# boost_gauge.net
KiCad netlist of a schematic drawn in EAGLE
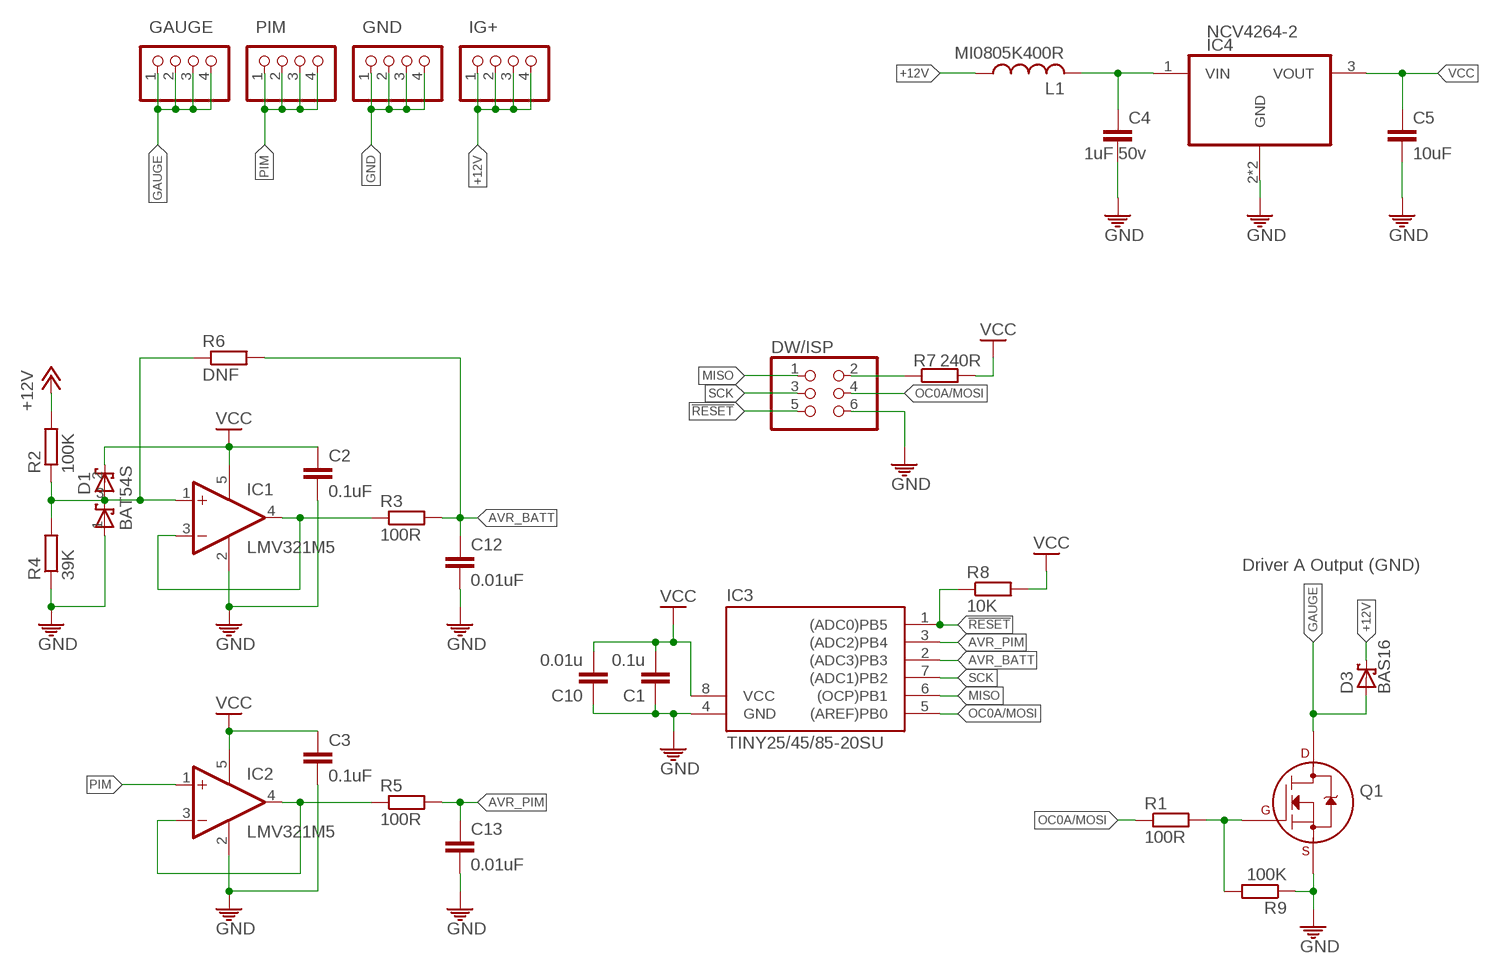
[diagram p0: schematic, sheet 1]

(export (version "E")
  (design (tool "Eeschema 10.0.6"))
  (components
    (comp (ref "C1")
      (value "0.1u")
      (footprint "eagle-import:C0603")
      (libsource (lib "eagle-import") (part "C-EUC0603"))
    )
    (comp (ref "C2")
      (value "0.1uF")
      (footprint "eagle-import:C0603")
      (libsource (lib "eagle-import") (part "C-EUC0603"))
    )
    (comp (ref "C3")
      (value "0.1uF")
      (footprint "eagle-import:C0603")
      (libsource (lib "eagle-import") (part "C-EUC0603"))
    )
    (comp (ref "C4")
      (value "1uF 50v")
      (footprint "eagle-import:C0603")
      (libsource (lib "eagle-import") (part "C-EUC0603"))
    )
    (comp (ref "C5")
      (value "10uF")
      (footprint "eagle-import:C1206")
      (libsource (lib "eagle-import") (part "C-EUC1206"))
    )
    (comp (ref "C10")
      (value "0.01u")
      (footprint "eagle-import:C0603")
      (libsource (lib "eagle-import") (part "C-EUC0603"))
    )
    (comp (ref "C12")
      (value "0.01uF")
      (footprint "eagle-import:C0603")
      (libsource (lib "eagle-import") (part "C-EUC0603"))
    )
    (comp (ref "C13")
      (value "0.01uF")
      (footprint "eagle-import:C0603")
      (libsource (lib "eagle-import") (part "C-EUC0603"))
    )
    (comp (ref "D1")
      (value "BAT54S")
      (footprint "eagle-import:SOT23")
      (libsource (lib "eagle-import") (part "BAT54S"))
    )
    (comp (ref "D3")
      (value "BAS16")
      (footprint "eagle-import:SOT23")
      (libsource (lib "eagle-import") (part "BAS16"))
    )
    (comp (ref "DW/ISP")
      (value "PINHD-2X3")
      (footprint "eagle-import:2X03")
      (libsource (lib "eagle-import") (part "PINHD-2X3"))
    )
    (comp (ref "GAUGE")
      (value "PCB-2")
      (footprint "eagle-import:PCB-2")
      (libsource (lib "eagle-import") (part "PCB-2"))
    )
    (comp (ref "GND")
      (value "PCB-2")
      (footprint "eagle-import:PCB-2")
      (libsource (lib "eagle-import") (part "PCB-2"))
    )
    (comp (ref "IC1")
      (value "LMV321M5")
      (footprint "eagle-import:SOT23-5")
      (libsource (lib "eagle-import") (part "LMV321?M5"))
    )
    (comp (ref "IC2")
      (value "LMV321M5")
      (footprint "eagle-import:SOT23-5")
      (libsource (lib "eagle-import") (part "LMV321?M5"))
    )
    (comp (ref "IC3")
      (value "TINY25/45/85-20SU")
      (footprint "eagle-import:SOIC8")
      (libsource (lib "eagle-import") (part "TINY25/45/85-20SU"))
    )
    (comp (ref "IC4")
      (value "NCV4264-2")
      (footprint "eagle-import:SOT223")
      (libsource (lib "eagle-import") (part "NCV4264-2"))
    )
    (comp (ref "IG+")
      (value "PCB-2")
      (footprint "eagle-import:PCB-2")
      (libsource (lib "eagle-import") (part "PCB-2"))
    )
    (comp (ref "L1")
      (value "MI0805K400R")
      (footprint "eagle-import:R0805")
      (libsource (lib "eagle-import") (part "MI0805K400R"))
    )
    (comp (ref "PIM")
      (value "PCB-2")
      (footprint "eagle-import:PCB-2")
      (libsource (lib "eagle-import") (part "PCB-2"))
    )
    (comp (ref "Q1")
      (value "2N7002A")
      (footprint "eagle-import:SOT23")
      (libsource (lib "eagle-import") (part "2N7002A"))
    )
    (comp (ref "R1")
      (value "100R")
      (footprint "eagle-import:R0603")
      (libsource (lib "eagle-import") (part "R-EU_R0603"))
    )
    (comp (ref "R2")
      (value "100K")
      (footprint "eagle-import:R0603")
      (libsource (lib "eagle-import") (part "R-EU_R0603"))
    )
    (comp (ref "R3")
      (value "100R")
      (footprint "eagle-import:R0603")
      (libsource (lib "eagle-import") (part "R-EU_R0603"))
    )
    (comp (ref "R4")
      (value "39K")
      (footprint "eagle-import:R0603")
      (libsource (lib "eagle-import") (part "R-EU_R0603"))
    )
    (comp (ref "R5")
      (value "100R")
      (footprint "eagle-import:R0603")
      (libsource (lib "eagle-import") (part "R-EU_R0603"))
    )
    (comp (ref "R6")
      (value "DNF")
      (footprint "eagle-import:R0603")
      (libsource (lib "eagle-import") (part "R-EU_R0603"))
    )
    (comp (ref "R7")
      (value "240R")
      (footprint "eagle-import:R0603")
      (libsource (lib "eagle-import") (part "R-EU_R0603"))
    )
    (comp (ref "R8")
      (value "10K")
      (footprint "eagle-import:R0603")
      (libsource (lib "eagle-import") (part "R-EU_R0603"))
    )
    (comp (ref "R9")
      (value "100K")
      (footprint "eagle-import:R0603")
      (libsource (lib "eagle-import") (part "R-EU_R0603"))
    )
  )
  (nets
    (net (code "1") (name "+12V") (class "Default")
      (node (ref "D3") (pin "3") (pinfunction "C_3") (pintype "passive"))
      (node (ref "IG+") (pin "1") (pinfunction "1_1") (pintype "passive"))
      (node (ref "IG+") (pin "2") (pinfunction "2_2") (pintype "passive"))
      (node (ref "IG+") (pin "3") (pinfunction "3_3") (pintype "passive"))
      (node (ref "IG+") (pin "4") (pinfunction "4_4") (pintype "passive"))
      (node (ref "L1") (pin "1") (pinfunction "1_1") (pintype "passive"))
      (node (ref "R2") (pin "2") (pinfunction "2_2") (pintype "passive"))
    )
    (net (code "2") (name "/~{RESET}") (class "Default")
      (node (ref "DW/ISP") (pin "5") (pinfunction "5_5") (pintype "passive"))
      (node (ref "IC3") (pin "1") (pinfunction "(ADC0)PB5_1") (pintype "bidirectional"))
      (node (ref "R8") (pin "1") (pinfunction "1_1") (pintype "passive"))
    )
    (net (code "3") (name "AVR_BATT") (class "Default")
      (node (ref "C12") (pin "1") (pinfunction "1_1") (pintype "passive"))
      (node (ref "IC3") (pin "2") (pinfunction "(ADC3)PB3_2") (pintype "bidirectional"))
      (node (ref "R3") (pin "2") (pinfunction "2_2") (pintype "passive"))
      (node (ref "R6") (pin "2") (pinfunction "2_2") (pintype "passive"))
    )
    (net (code "4") (name "AVR_PIM") (class "Default")
      (node (ref "C13") (pin "1") (pinfunction "1_1") (pintype "passive"))
      (node (ref "IC3") (pin "3") (pinfunction "(ADC2)PB4_3") (pintype "bidirectional"))
      (node (ref "R5") (pin "2") (pinfunction "2_2") (pintype "passive"))
    )
    (net (code "5") (name "GAUGE") (class "Default")
      (node (ref "D3") (pin "1") (pinfunction "A_1") (pintype "passive"))
      (node (ref "GAUGE") (pin "1") (pinfunction "1_1") (pintype "passive"))
      (node (ref "GAUGE") (pin "2") (pinfunction "2_2") (pintype "passive"))
      (node (ref "GAUGE") (pin "3") (pinfunction "3_3") (pintype "passive"))
      (node (ref "GAUGE") (pin "4") (pinfunction "4_4") (pintype "passive"))
      (node (ref "Q1") (pin "3") (pinfunction "D_3") (pintype "bidirectional"))
    )
    (net (code "6") (name "GND") (class "Default")
      (node (ref "C1") (pin "1") (pinfunction "1_1") (pintype "passive"))
      (node (ref "C10") (pin "1") (pinfunction "1_1") (pintype "passive"))
      (node (ref "C12") (pin "2") (pinfunction "2_2") (pintype "passive"))
      (node (ref "C13") (pin "2") (pinfunction "2_2") (pintype "passive"))
      (node (ref "C2") (pin "2") (pinfunction "2_2") (pintype "passive"))
      (node (ref "C3") (pin "2") (pinfunction "2_2") (pintype "passive"))
      (node (ref "C4") (pin "2") (pinfunction "2_2") (pintype "passive"))
      (node (ref "C5") (pin "2") (pinfunction "2_2") (pintype "passive"))
      (node (ref "D1") (pin "1") (pinfunction "A1_1") (pintype "passive"))
      (node (ref "DW/ISP") (pin "6") (pinfunction "6_6") (pintype "passive"))
      (node (ref "GND") (pin "1") (pinfunction "1_1") (pintype "passive"))
      (node (ref "GND") (pin "2") (pinfunction "2_2") (pintype "passive"))
      (node (ref "GND") (pin "3") (pinfunction "3_3") (pintype "passive"))
      (node (ref "GND") (pin "4") (pinfunction "4_4") (pintype "passive"))
      (node (ref "IC1") (pin "2") (pinfunction "V-_2") (pintype "power_in"))
      (node (ref "IC2") (pin "2") (pinfunction "V-_2") (pintype "power_in"))
      (node (ref "IC3") (pin "4") (pinfunction "GND_4") (pintype "power_in"))
      (node (ref "IC4") (pin "2") (pinfunction "GND_2") (pintype "power_in"))
      (node (ref "IC4") (pin "4") (pinfunction "GND_4") (pintype "power_in"))
      (node (ref "Q1") (pin "2") (pinfunction "S_2") (pintype "bidirectional"))
      (node (ref "R4") (pin "1") (pinfunction "1_1") (pintype "passive"))
      (node (ref "R9") (pin "1") (pinfunction "1_1") (pintype "passive"))
    )
    (net (code "7") (name "MISO") (class "Default")
      (node (ref "DW/ISP") (pin "1") (pinfunction "1_1") (pintype "passive"))
      (node (ref "IC3") (pin "6") (pinfunction "(OCP)PB1_6") (pintype "bidirectional"))
    )
    (net (code "8") (name "Net-(D1-C1A2)") (class "Default")
      (node (ref "D1") (pin "3") (pinfunction "C1A2_3") (pintype "passive"))
      (node (ref "IC1") (pin "1") (pinfunction "+IN_1") (pintype "input"))
      (node (ref "R2") (pin "1") (pinfunction "1_1") (pintype "passive"))
      (node (ref "R4") (pin "2") (pinfunction "2_2") (pintype "passive"))
      (node (ref "R6") (pin "1") (pinfunction "1_1") (pintype "passive"))
    )
    (net (code "9") (name "Net-(DW/ISP-Pad2)") (class "Default")
      (node (ref "DW/ISP") (pin "2") (pinfunction "2_2") (pintype "passive"))
      (node (ref "R7") (pin "1") (pinfunction "1_1") (pintype "passive"))
    )
    (net (code "10") (name "Net-(IC1--IN)") (class "Default")
      (node (ref "IC1") (pin "3") (pinfunction "-IN_3") (pintype "input"))
      (node (ref "IC1") (pin "4") (pinfunction "OUT_4") (pintype "output"))
      (node (ref "R3") (pin "1") (pinfunction "1_1") (pintype "passive"))
    )
    (net (code "11") (name "Net-(IC2--IN)") (class "Default")
      (node (ref "IC2") (pin "3") (pinfunction "-IN_3") (pintype "input"))
      (node (ref "IC2") (pin "4") (pinfunction "OUT_4") (pintype "output"))
      (node (ref "R5") (pin "1") (pinfunction "1_1") (pintype "passive"))
    )
    (net (code "12") (name "Net-(IC4-VIN)") (class "Default")
      (node (ref "C4") (pin "1") (pinfunction "1_1") (pintype "passive"))
      (node (ref "IC4") (pin "1") (pinfunction "VIN_1") (pintype "power_in"))
      (node (ref "L1") (pin "2") (pinfunction "2_2") (pintype "passive"))
    )
    (net (code "13") (name "Net-(Q1-G)") (class "Default")
      (node (ref "Q1") (pin "1") (pinfunction "G_1") (pintype "tri_state"))
      (node (ref "R1") (pin "2") (pinfunction "2_2") (pintype "passive"))
      (node (ref "R9") (pin "2") (pinfunction "2_2") (pintype "passive"))
    )
    (net (code "14") (name "OC0A{slash}MOSI") (class "Default")
      (node (ref "DW/ISP") (pin "4") (pinfunction "4_4") (pintype "passive"))
      (node (ref "IC3") (pin "5") (pinfunction "(AREF)PB0_5") (pintype "bidirectional"))
      (node (ref "R1") (pin "1") (pinfunction "1_1") (pintype "passive"))
    )
    (net (code "15") (name "PIM") (class "Default")
      (node (ref "IC2") (pin "1") (pinfunction "+IN_1") (pintype "input"))
      (node (ref "PIM") (pin "1") (pinfunction "1_1") (pintype "passive"))
      (node (ref "PIM") (pin "2") (pinfunction "2_2") (pintype "passive"))
      (node (ref "PIM") (pin "3") (pinfunction "3_3") (pintype "passive"))
      (node (ref "PIM") (pin "4") (pinfunction "4_4") (pintype "passive"))
    )
    (net (code "16") (name "SCK") (class "Default")
      (node (ref "DW/ISP") (pin "3") (pinfunction "3_3") (pintype "passive"))
      (node (ref "IC3") (pin "7") (pinfunction "(ADC1)PB2_7") (pintype "bidirectional"))
    )
    (net (code "17") (name "VCC") (class "Default")
      (node (ref "C1") (pin "2") (pinfunction "2_2") (pintype "passive"))
      (node (ref "C10") (pin "2") (pinfunction "2_2") (pintype "passive"))
      (node (ref "C2") (pin "1") (pinfunction "1_1") (pintype "passive"))
      (node (ref "C3") (pin "1") (pinfunction "1_1") (pintype "passive"))
      (node (ref "C5") (pin "1") (pinfunction "1_1") (pintype "passive"))
      (node (ref "D1") (pin "2") (pinfunction "C2_2") (pintype "passive"))
      (node (ref "IC1") (pin "5") (pinfunction "V+_5") (pintype "power_in"))
      (node (ref "IC2") (pin "5") (pinfunction "V+_5") (pintype "power_in"))
      (node (ref "IC3") (pin "8") (pinfunction "VCC_8") (pintype "power_in"))
      (node (ref "IC4") (pin "3") (pinfunction "VOUT_3") (pintype "power_in"))
      (node (ref "R7") (pin "2") (pinfunction "2_2") (pintype "passive"))
      (node (ref "R8") (pin "2") (pinfunction "2_2") (pintype "passive"))
    )
  )
)
